# iSensor.net
KiCad netlist of a schematic drawn in Altium Designer
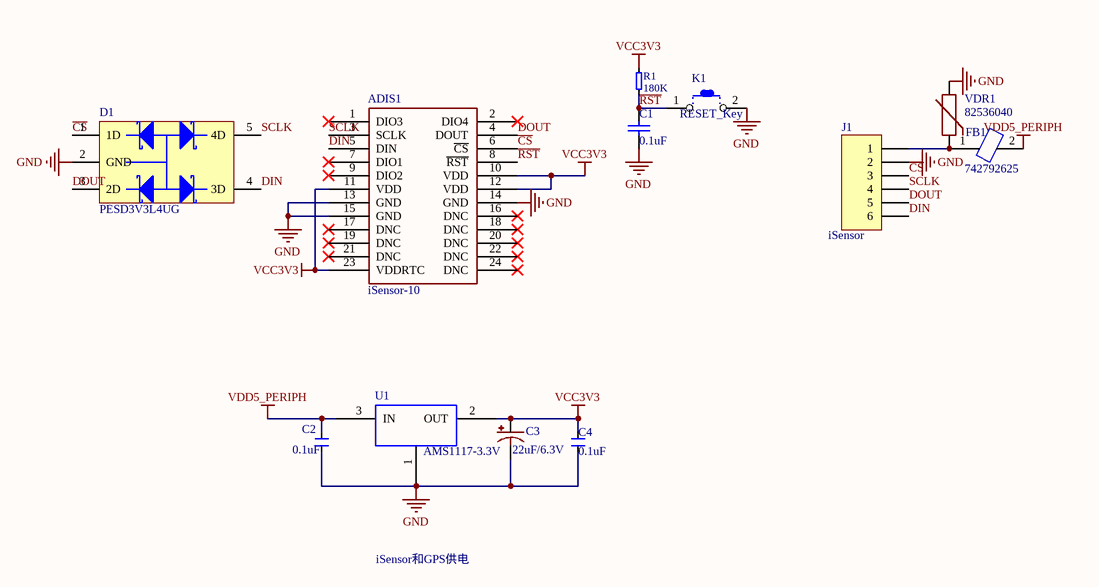
[diagram p0: iSensor.SchDoc]

(export (version "E")
  (design (tool "Eeschema 10.0.6"))
  (components
    (comp (ref "ADIS1")
      (value "iSensor-10")
      (footprint "研发中心PCB库文件:iSensor")
      (libsource (lib "研发中心原理图库文件") (part "iSensor-10"))
    )
    (comp (ref "C1")
      (value "0.1uF")
      (footprint "研发中心PCB库文件:0603C")
      (libsource (lib "研发中心原理图库文件") (part "Cap"))
    )
    (comp (ref "C2") (value "0.1uF") (footprint "0603C") (libsource (lib "研发中心原理图库文件") (part "C")))
    (comp (ref "C3") (value "22uF/6.3V") (footprint "3528/B") (libsource (lib "研发中心原理图库文件") (part "C-POLAR")))
    (comp (ref "C4") (value "0.1uF") (footprint "0603C") (libsource (lib "研发中心原理图库文件") (part "C")))
    (comp (ref "D1")
      (value "PESD3V3L4UG")
      (footprint "SOT353")
      (libsource (lib "研发中心原理图库文件") (part "PESD3V3L4UG"))
    )
    (comp (ref "FB1")
      (value "742792625")
      (footprint "研发中心PCB库文件:0603-FB")
      (libsource (lib "研发中心原理图库文件") (part "FB"))
    )
    (comp (ref "J1") (value "iSensor") (footprint "GH1.25-6") (libsource (lib "研发中心原理图库文件") (part "HEAD1X6")))
    (comp (ref "K1")
      (value "RESET_Key")
      (footprint "研发中心PCB库文件:3*6*2.5 SMD")
      (libsource (lib "研发中心原理图库文件") (part "RESET_Key"))
    )
    (comp (ref "R1") (value "180K") (footprint "研发中心PCB库文件:0603R") (libsource (lib "研发中心原理图库文件") (part "R")))
    (comp (ref "U1")
      (value "AMS1117-3.3V")
      (footprint "SOT223")
      (description "5V-3.3V")
      (libsource (lib "研发中心原理图库文件") (part "AS1117M3-3.3V"))
    )
    (comp (ref "VDR1")
      (value "82536040")
      (footprint "研发中心PCB库文件:0603R")
      (libsource (lib "研发中心原理图库文件") (part "Varistor"))
    )
  )
  (nets
    (net (code "1") (name "/DIN") (class "Default")
      (node (ref "ADIS1") (pin "5") (pinfunction "DIN_5") (pintype "passive"))
      (node (ref "D1") (pin "4") (pinfunction "3D_4") (pintype "passive"))
      (node (ref "J1") (pin "6") (pinfunction "6_6") (pintype "passive"))
    )
    (net (code "2") (name "/DOUT") (class "Default")
      (node (ref "ADIS1") (pin "4") (pinfunction "DOUT_4") (pintype "passive"))
      (node (ref "D1") (pin "3") (pinfunction "2D_3") (pintype "passive"))
      (node (ref "J1") (pin "5") (pinfunction "5_5") (pintype "passive"))
    )
    (net (code "3") (name "/SCLK") (class "Default")
      (node (ref "ADIS1") (pin "3") (pinfunction "SCLK_3") (pintype "passive"))
      (node (ref "D1") (pin "5") (pinfunction "4D_5") (pintype "passive"))
      (node (ref "J1") (pin "4") (pinfunction "4_4") (pintype "passive"))
    )
    (net (code "4") (name "/~{CS}") (class "Default")
      (node (ref "ADIS1") (pin "6") (pinfunction "~{CS}_6") (pintype "passive"))
      (node (ref "D1") (pin "1") (pinfunction "1D_1") (pintype "passive"))
      (node (ref "J1") (pin "3") (pinfunction "3_3") (pintype "passive"))
    )
    (net (code "5") (name "/~{RST}") (class "Default")
      (node (ref "ADIS1") (pin "8") (pinfunction "~{RST}_8") (pintype "passive"))
      (node (ref "C1") (pin "2") (pinfunction "2_2") (pintype "passive"))
      (node (ref "K1") (pin "1") (pinfunction "1_1") (pintype "passive"))
      (node (ref "R1") (pin "1") (pintype "passive"))
    )
    (net (code "6") (name "GND") (class "Default")
      (node (ref "ADIS1") (pin "13") (pinfunction "GND_13") (pintype "passive"))
      (node (ref "ADIS1") (pin "14") (pinfunction "GND_14") (pintype "passive"))
      (node (ref "ADIS1") (pin "15") (pinfunction "GND_15") (pintype "passive"))
      (node (ref "C1") (pin "1") (pinfunction "1_1") (pintype "passive"))
      (node (ref "C2") (pin "1") (pintype "passive"))
      (node (ref "C3") (pin "2") (pinfunction "2_2") (pintype "passive"))
      (node (ref "C4") (pin "1") (pintype "passive"))
      (node (ref "D1") (pin "2") (pinfunction "GND_2") (pintype "passive"))
      (node (ref "J1") (pin "2") (pinfunction "2_2") (pintype "passive"))
      (node (ref "K1") (pin "2") (pinfunction "2_2") (pintype "passive"))
      (node (ref "U1") (pin "1") (pinfunction "COM_1") (pintype "passive"))
      (node (ref "VDR1") (pin "1") (pinfunction "1_1") (pintype "passive"))
    )
    (net (code "7") (name "Net-(FB1-Pad1)") (class "Default")
      (node (ref "FB1") (pin "1") (pinfunction "1_1") (pintype "passive"))
      (node (ref "J1") (pin "1") (pinfunction "1_1") (pintype "passive"))
      (node (ref "VDR1") (pin "2") (pinfunction "2_2") (pintype "passive"))
    )
    (net (code "8") (name "VCC3V3") (class "Default")
      (node (ref "ADIS1") (pin "10") (pinfunction "VDD_10") (pintype "passive"))
      (node (ref "ADIS1") (pin "11") (pinfunction "VDD_11") (pintype "passive"))
      (node (ref "ADIS1") (pin "12") (pinfunction "VDD_12") (pintype "passive"))
      (node (ref "ADIS1") (pin "23") (pinfunction "VDDRTC_23") (pintype "passive"))
      (node (ref "C3") (pin "1") (pinfunction "1_1") (pintype "passive"))
      (node (ref "C4") (pin "2") (pintype "passive"))
      (node (ref "R1") (pin "2") (pintype "passive"))
      (node (ref "U1") (pin "2") (pinfunction "OUT_2") (pintype "passive"))
    )
    (net (code "9") (name "VDD5_PERIPH") (class "Default")
      (node (ref "C2") (pin "2") (pintype "passive"))
      (node (ref "FB1") (pin "2") (pinfunction "2_2") (pintype "passive"))
      (node (ref "U1") (pin "3") (pinfunction "IN_3") (pintype "passive"))
    )
    (net (code "10") (name "unconnected-(ADIS1-DIO1-Pad7)") (class "Default")
      (node (ref "ADIS1") (pin "7") (pinfunction "DIO1_7") (pintype "passive+no_connect"))
    )
    (net (code "11") (name "unconnected-(ADIS1-DIO2-Pad9)") (class "Default")
      (node (ref "ADIS1") (pin "9") (pinfunction "DIO2_9") (pintype "passive+no_connect"))
    )
    (net (code "12") (name "unconnected-(ADIS1-DIO3-Pad1)") (class "Default")
      (node (ref "ADIS1") (pin "1") (pinfunction "DIO3_1") (pintype "passive+no_connect"))
    )
    (net (code "13") (name "unconnected-(ADIS1-DIO4-Pad2)") (class "Default")
      (node (ref "ADIS1") (pin "2") (pinfunction "DIO4_2") (pintype "passive+no_connect"))
    )
    (net (code "14") (name "unconnected-(ADIS1-DNC-Pad16)") (class "Default")
      (node (ref "ADIS1") (pin "16") (pinfunction "DNC_16") (pintype "passive+no_connect"))
    )
    (net (code "15") (name "unconnected-(ADIS1-DNC-Pad17)") (class "Default")
      (node (ref "ADIS1") (pin "17") (pinfunction "DNC_17") (pintype "passive+no_connect"))
    )
    (net (code "16") (name "unconnected-(ADIS1-DNC-Pad18)") (class "Default")
      (node (ref "ADIS1") (pin "18") (pinfunction "DNC_18") (pintype "passive+no_connect"))
    )
    (net (code "17") (name "unconnected-(ADIS1-DNC-Pad19)") (class "Default")
      (node (ref "ADIS1") (pin "19") (pinfunction "DNC_19") (pintype "passive+no_connect"))
    )
    (net (code "18") (name "unconnected-(ADIS1-DNC-Pad20)") (class "Default")
      (node (ref "ADIS1") (pin "20") (pinfunction "DNC_20") (pintype "passive+no_connect"))
    )
    (net (code "19") (name "unconnected-(ADIS1-DNC-Pad21)") (class "Default")
      (node (ref "ADIS1") (pin "21") (pinfunction "DNC_21") (pintype "passive+no_connect"))
    )
    (net (code "20") (name "unconnected-(ADIS1-DNC-Pad22)") (class "Default")
      (node (ref "ADIS1") (pin "22") (pinfunction "DNC_22") (pintype "passive+no_connect"))
    )
    (net (code "21") (name "unconnected-(ADIS1-DNC-Pad24)") (class "Default")
      (node (ref "ADIS1") (pin "24") (pinfunction "DNC_24") (pintype "passive+no_connect"))
    )
  )
)
